# KalamBoard.net
KiCad netlist of a schematic drawn in EAGLE
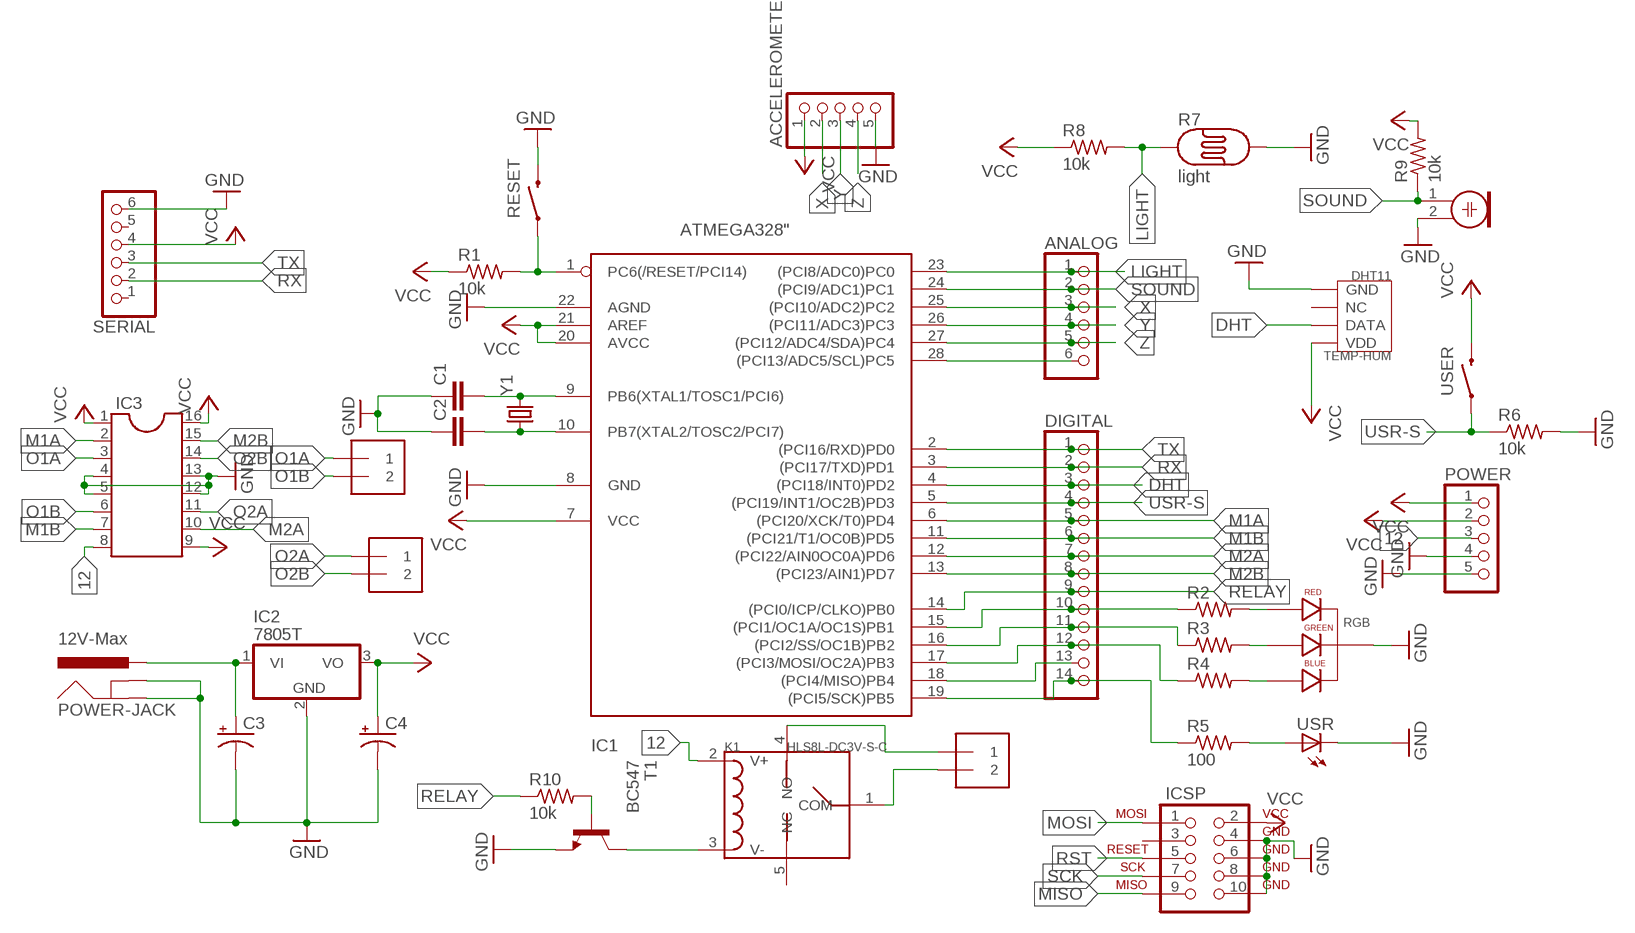
[diagram p0: schematic, sheet 1]

(export (version "E")
  (design (tool "Eeschema 10.0.6"))
  (components
    (comp (ref "ACCELEROMETER")
      (value "PINHD-1X5")
      (footprint "eagle-import:1X05")
      (libsource (lib "eagle-import") (part "PINHD-1X5"))
    )
    (comp (ref "ANALOG")
      (value "PINHD-1X6")
      (footprint "eagle-import:1X06")
      (libsource (lib "eagle-import") (part "PINHD-1X6"))
    )
    (comp (ref "C1")
      (value "0.1UF-50V-20%(PTH)KIT-EZ")
      (footprint "eagle-import:CAP-PTH-SMALL-KIT")
      (libsource (lib "eagle-import") (part "0.1UF-50V-20%(PTH)KIT-EZ"))
    )
    (comp (ref "C2")
      (value "0.1UF-50V-20%(PTH)KIT-EZ")
      (footprint "eagle-import:CAP-PTH-SMALL-KIT")
      (libsource (lib "eagle-import") (part "0.1UF-50V-20%(PTH)KIT-EZ"))
    )
    (comp (ref "C3")
      (value "10UF-25V-20%(PTH)")
      (footprint "eagle-import:CPOL-RADIAL-10UF-25V")
      (libsource (lib "eagle-import") (part "10UF-25V-20%(PTH)"))
    )
    (comp (ref "C4")
      (value "10UF-25V-20%(PTH)")
      (footprint "eagle-import:CPOL-RADIAL-10UF-25V")
      (libsource (lib "eagle-import") (part "10UF-25V-20%(PTH)"))
    )
    (comp (ref "DIGITAL")
      (value "PINHD-1X14")
      (footprint "eagle-import:1X14")
      (libsource (lib "eagle-import") (part "PINHD-1X14"))
    )
    (comp (ref "IC1")
      (value "ATMEGA328\"")
      (footprint "eagle-import:ATMEGA328")
      (libsource (lib "eagle-import") (part "ATMEGA328{dblquote}"))
    )
    (comp (ref "IC2")
      (value "7805T")
      (footprint "eagle-import:TO220H")
      (libsource (lib "eagle-import") (part "78T05"))
    )
    (comp (ref "IC3")
      (value "DIL16S")
      (footprint "eagle-import:SOCKET-16")
      (libsource (lib "eagle-import") (part "DIL16S"))
    )
    (comp (ref "ICSP")
      (value "AVR_SPI_PROG2PTH")
      (footprint "eagle-import:AVR_ICSP")
      (libsource (lib "eagle-import") (part "AVR_SPI_PROG2PTH"))
    )
    (comp (ref "K1")
      (value "HLS8L-DC3V-S-C")
      (footprint "eagle-import:REY5-19.0X15.0X15.0MM")
      (libsource (lib "eagle-import") (part "RELAY-HLS8L-DC3V-S-C(5P-19X15MM)"))
    )
    (comp (ref "MOTOR1")
      (value "1X2-3.5MM")
      (footprint "eagle-import:1X2-3.5MM")
      (libsource (lib "eagle-import") (part "1X2-3.5MM"))
    )
    (comp (ref "MOTOR2")
      (value "1X2-3.5MM")
      (footprint "eagle-import:1X2-3.5MM")
      (libsource (lib "eagle-import") (part "1X2-3.5MM"))
    )
    (comp (ref "POWER")
      (value "PINHD-1X5")
      (footprint "eagle-import:1X05")
      (libsource (lib "eagle-import") (part "PINHD-1X5"))
    )
    (comp (ref "POWER-JACK")
      (value "12V-Max")
      (footprint "eagle-import:POWER_JACK")
      (libsource (lib "eagle-import") (part "POWER_JACK{dblquote}"))
    )
    (comp (ref "R1")
      (value "10k")
      (footprint "eagle-import:RESISTOR")
      (libsource (lib "eagle-import") (part "RESISTOR1/6WATT"))
    )
    (comp (ref "R2")
      (value "RESISTOR1/6WATT")
      (footprint "eagle-import:RESISTOR")
      (libsource (lib "eagle-import") (part "RESISTOR1/6WATT"))
    )
    (comp (ref "R3")
      (value "RESISTOR1/6WATT")
      (footprint "eagle-import:RESISTOR")
      (libsource (lib "eagle-import") (part "RESISTOR1/6WATT"))
    )
    (comp (ref "R4")
      (value "RESISTOR1/6WATT")
      (footprint "eagle-import:RESISTOR")
      (libsource (lib "eagle-import") (part "RESISTOR1/6WATT"))
    )
    (comp (ref "R5")
      (value "100")
      (footprint "eagle-import:RESISTOR")
      (libsource (lib "eagle-import") (part "RESISTOR1/6WATT"))
    )
    (comp (ref "R6")
      (value "10k")
      (footprint "eagle-import:RESISTOR")
      (libsource (lib "eagle-import") (part "RESISTOR1/6WATT"))
    )
    (comp (ref "R7")
      (value "light")
      (footprint "eagle-import:PHOTOCELL")
      (libsource (lib "eagle-import") (part "PHOTOCELLPTH"))
    )
    (comp (ref "R8")
      (value "10k")
      (footprint "eagle-import:RESISTOR")
      (libsource (lib "eagle-import") (part "RESISTOR1/6WATT"))
    )
    (comp (ref "R9")
      (value "10k")
      (footprint "eagle-import:RESISTOR")
      (libsource (lib "eagle-import") (part "RESISTOR1/6WATT"))
    )
    (comp (ref "R10")
      (value "10k")
      (footprint "eagle-import:RESISTOR")
      (libsource (lib "eagle-import") (part "RESISTOR1/6WATT"))
    )
    (comp (ref "RELAY")
      (value "1X2-3.5MM")
      (footprint "eagle-import:1X2-3.5MM")
      (libsource (lib "eagle-import") (part "1X2-3.5MM"))
    )
    (comp (ref "RESET")
      (value "MOMENTARY_SWITCH\"")
      (footprint "eagle-import:MOMENTARY_SWITCH")
      (libsource (lib "eagle-import") (part "MOMENTARY_SWITCH{dblquote}"))
    )
    (comp (ref "RGB")
      (value "LED-RGB-CC-THRUDIFFUSE")
      (footprint "eagle-import:LED-RGB-THRU")
      (libsource (lib "eagle-import") (part "LED-RGB-CC-THRUDIFFUSE"))
    )
    (comp (ref "SERIAL")
      (value "PINHD-1X6")
      (footprint "eagle-import:1X06")
      (libsource (lib "eagle-import") (part "PINHD-1X6"))
    )
    (comp (ref "SOUND")
      (value "ELECTRET_MICROPHON-F6050AP")
      (footprint "eagle-import:F6050AP")
      (libsource (lib "eagle-import") (part "ELECTRET_MICROPHON-F6050AP"))
    )
    (comp (ref "T1")
      (value "BC547")
      (footprint "eagle-import:TO92")
      (libsource (lib "eagle-import") (part "BC547"))
    )
    (comp (ref "TEMP-HUM")
      (value "DHT11")
      (footprint "eagle-import:SNR4-2.54-15.5X12.0X5.5MM")
      (libsource (lib "eagle-import") (part "TEM-HUM-DHT11(4P-15.5X12.0MM)"))
    )
    (comp (ref "USER")
      (value "MOMENTARY_SWITCH\"")
      (footprint "eagle-import:MOMENTARY_SWITCH")
      (libsource (lib "eagle-import") (part "MOMENTARY_SWITCH{dblquote}"))
    )
    (comp (ref "USR")
      (value "LED3MM")
      (footprint "eagle-import:LED")
      (libsource (lib "eagle-import") (part "LED3MM"))
    )
    (comp (ref "Y1")
      (value "CRYSTALHC49US")
      (footprint "eagle-import:HC49US")
      (libsource (lib "eagle-import") (part "CRYSTALHC49US"))
    )
  )
  (nets
    (net (code "1") (name "12") (class "Default")
      (node (ref "C3") (pin "1") (pinfunction "+_1") (pintype "passive"))
      (node (ref "IC2") (pin "1") (pinfunction "VI_1") (pintype "input"))
      (node (ref "IC3") (pin "8") (pinfunction "8_8") (pintype "passive"))
      (node (ref "K1") (pin "2") (pinfunction "V+_2") (pintype "bidirectional"))
      (node (ref "POWER") (pin "3") (pinfunction "3_3") (pintype "passive"))
      (node (ref "POWER-JACK") (pin "PWR") (pinfunction "PWR_PWR") (pintype "bidirectional"))
    )
    (net (code "2") (name "DHT") (class "Default")
      (node (ref "DIGITAL") (pin "3") (pinfunction "3_3") (pintype "passive"))
      (node (ref "IC1") (pin "4") (pinfunction "(PCI18/INT0)PD2_4") (pintype "bidirectional"))
      (node (ref "TEMP-HUM") (pin "2") (pinfunction "DATA_2") (pintype "bidirectional"))
    )
    (net (code "3") (name "GND") (class "Default")
      (node (ref "ACCELEROMETER") (pin "5") (pinfunction "5_5") (pintype "passive"))
      (node (ref "C1") (pin "1") (pinfunction "1_1") (pintype "passive"))
      (node (ref "C2") (pin "1") (pinfunction "1_1") (pintype "passive"))
      (node (ref "C3") (pin "2") (pinfunction "-_2") (pintype "passive"))
      (node (ref "C4") (pin "2") (pinfunction "-_2") (pintype "passive"))
      (node (ref "IC1") (pin "22") (pinfunction "AGND_22") (pintype "bidirectional"))
      (node (ref "IC1") (pin "8") (pinfunction "GND_8") (pintype "bidirectional"))
      (node (ref "IC2") (pin "2") (pinfunction "GND_2") (pintype "passive"))
      (node (ref "IC3") (pin "12") (pinfunction "12_12") (pintype "passive"))
      (node (ref "IC3") (pin "13") (pinfunction "13_13") (pintype "passive"))
      (node (ref "IC3") (pin "4") (pinfunction "4_4") (pintype "passive"))
      (node (ref "IC3") (pin "5") (pinfunction "5_5") (pintype "passive"))
      (node (ref "ICSP") (pin "10") (pinfunction "GND_10") (pintype "power_in"))
      (node (ref "ICSP") (pin "4") (pinfunction "GND_4") (pintype "power_in"))
      (node (ref "ICSP") (pin "6") (pinfunction "GND_6") (pintype "power_in"))
      (node (ref "ICSP") (pin "8") (pinfunction "GND_8") (pintype "power_in"))
      (node (ref "POWER") (pin "4") (pinfunction "4_4") (pintype "passive"))
      (node (ref "POWER") (pin "5") (pinfunction "5_5") (pintype "passive"))
      (node (ref "POWER-JACK") (pin "GND") (pinfunction "GND_GND") (pintype "bidirectional"))
      (node (ref "POWER-JACK") (pin "GNDBREAK") (pinfunction "GNDBREAK_GNDBREAK") (pintype "bidirectional"))
      (node (ref "R6") (pin "2") (pinfunction "2_2") (pintype "passive"))
      (node (ref "R7") (pin "2") (pinfunction "P$2_2") (pintype "bidirectional"))
      (node (ref "RESET") (pin "3") (pinfunction "2_3") (pintype "passive"))
      (node (ref "RGB") (pin "2") (pinfunction "CATHODE_2") (pintype "bidirectional"))
      (node (ref "SERIAL") (pin "6") (pinfunction "6_6") (pintype "passive"))
      (node (ref "SOUND") (pin "2") (pinfunction "2_2") (pintype "passive"))
      (node (ref "T1") (pin "1") (pinfunction "E_1") (pintype "passive"))
      (node (ref "TEMP-HUM") (pin "4") (pinfunction "GND_4") (pintype "power_in"))
      (node (ref "USR") (pin "K") (pinfunction "C_K") (pintype "passive"))
    )
    (net (code "4") (name "LIGHT") (class "Default")
      (node (ref "ANALOG") (pin "1") (pinfunction "1_1") (pintype "passive"))
      (node (ref "IC1") (pin "23") (pinfunction "(PCI8/ADC0)PC0_23") (pintype "bidirectional"))
      (node (ref "R7") (pin "1") (pinfunction "P$1_1") (pintype "bidirectional"))
      (node (ref "R8") (pin "2") (pinfunction "2_2") (pintype "passive"))
    )
    (net (code "5") (name "M1A") (class "Default")
      (node (ref "DIGITAL") (pin "5") (pinfunction "5_5") (pintype "passive"))
      (node (ref "IC1") (pin "6") (pinfunction "(PCI20/XCK/T0)PD4_6") (pintype "bidirectional"))
      (node (ref "IC3") (pin "2") (pinfunction "2_2") (pintype "passive"))
    )
    (net (code "6") (name "M1B") (class "Default")
      (node (ref "DIGITAL") (pin "6") (pinfunction "6_6") (pintype "passive"))
      (node (ref "IC1") (pin "11") (pinfunction "(PCI21/T1/OC0B)PD5_11") (pintype "bidirectional"))
      (node (ref "IC3") (pin "7") (pinfunction "7_7") (pintype "passive"))
    )
    (net (code "7") (name "M2A") (class "Default")
      (node (ref "DIGITAL") (pin "7") (pinfunction "7_7") (pintype "passive"))
      (node (ref "IC1") (pin "12") (pinfunction "(PCI22/AIN0OC0A)PD6_12") (pintype "bidirectional"))
      (node (ref "IC3") (pin "10") (pinfunction "10_10") (pintype "passive"))
    )
    (net (code "8") (name "M2B") (class "Default")
      (node (ref "DIGITAL") (pin "8") (pinfunction "8_8") (pintype "passive"))
      (node (ref "IC1") (pin "13") (pinfunction "(PCI23/AIN1)PD7_13") (pintype "bidirectional"))
      (node (ref "IC3") (pin "15") (pinfunction "15_15") (pintype "passive"))
    )
    (net (code "9") (name "MISO") (class "Default")
      (node (ref "DIGITAL") (pin "13") (pinfunction "13_13") (pintype "passive"))
      (node (ref "IC1") (pin "18") (pinfunction "(PCI4/MISO)PB4_18") (pintype "bidirectional"))
      (node (ref "ICSP") (pin "9") (pinfunction "MISO_9") (pintype "passive"))
    )
    (net (code "10") (name "MOSI") (class "Default")
      (node (ref "DIGITAL") (pin "12") (pinfunction "12_12") (pintype "passive"))
      (node (ref "IC1") (pin "17") (pinfunction "(PCI3/MOSI/OC2A)PB3_17") (pintype "bidirectional"))
      (node (ref "ICSP") (pin "1") (pinfunction "MOSI_1") (pintype "passive"))
      (node (ref "R4") (pin "1") (pinfunction "1_1") (pintype "passive"))
    )
    (net (code "11") (name "Net-(IC1-(PCI1{slash}OC1A{slash}OC1S)PB1)") (class "Default")
      (node (ref "DIGITAL") (pin "10") (pinfunction "10_10") (pintype "passive"))
      (node (ref "IC1") (pin "15") (pinfunction "(PCI1/OC1A/OC1S)PB1_15") (pintype "bidirectional"))
      (node (ref "R2") (pin "1") (pinfunction "1_1") (pintype "passive"))
    )
    (net (code "12") (name "Net-(IC1-(PCI2{slash}SS{slash}OC1B)PB2)") (class "Default")
      (node (ref "DIGITAL") (pin "11") (pinfunction "11_11") (pintype "passive"))
      (node (ref "IC1") (pin "16") (pinfunction "(PCI2/SS/OC1B)PB2_16") (pintype "bidirectional"))
      (node (ref "R3") (pin "1") (pinfunction "1_1") (pintype "passive"))
    )
    (net (code "13") (name "Net-(IC1-(PCI13{slash}ADC5{slash}SCL)PC5)") (class "Default")
      (node (ref "ANALOG") (pin "6") (pinfunction "6_6") (pintype "passive"))
      (node (ref "IC1") (pin "28") (pinfunction "(PCI13/ADC5/SCL)PC5_28") (pintype "bidirectional"))
    )
    (net (code "14") (name "Net-(IC1-PB6(XTAL1{slash}TOSC1{slash}PCI6))") (class "Default")
      (node (ref "C1") (pin "2") (pinfunction "2_2") (pintype "passive"))
      (node (ref "IC1") (pin "9") (pinfunction "PB6(XTAL1/TOSC1/PCI6)_9") (pintype "bidirectional"))
      (node (ref "Y1") (pin "2") (pinfunction "2_2") (pintype "passive"))
    )
    (net (code "15") (name "Net-(IC1-PB7(XTAL2{slash}TOSC2{slash}PCI7))") (class "Default")
      (node (ref "C2") (pin "2") (pinfunction "2_2") (pintype "passive"))
      (node (ref "IC1") (pin "10") (pinfunction "PB7(XTAL2/TOSC2/PCI7)_10") (pintype "bidirectional"))
      (node (ref "Y1") (pin "1") (pinfunction "1_1") (pintype "passive"))
    )
    (net (code "16") (name "Net-(K1-COM)") (class "Default")
      (node (ref "K1") (pin "1") (pinfunction "COM_1") (pintype "bidirectional"))
      (node (ref "RELAY") (pin "2") (pinfunction "2_2") (pintype "passive"))
    )
    (net (code "17") (name "Net-(K1-NO)") (class "Default")
      (node (ref "K1") (pin "4") (pinfunction "NO_4") (pintype "bidirectional"))
      (node (ref "RELAY") (pin "1") (pinfunction "1_1") (pintype "passive"))
    )
    (net (code "18") (name "Net-(K1-V-)") (class "Default")
      (node (ref "K1") (pin "3") (pinfunction "V-_3") (pintype "bidirectional"))
      (node (ref "T1") (pin "3") (pinfunction "C_3") (pintype "passive"))
    )
    (net (code "19") (name "Net-(R5-Pad2)") (class "Default")
      (node (ref "R5") (pin "2") (pinfunction "2_2") (pintype "passive"))
      (node (ref "USR") (pin "A") (pinfunction "A_A") (pintype "passive"))
    )
    (net (code "20") (name "Net-(RGB-BLUE_CATHODE)") (class "Default")
      (node (ref "R4") (pin "2") (pinfunction "2_2") (pintype "passive"))
      (node (ref "RGB") (pin "4") (pinfunction "BLUE_CATHODE_4") (pintype "bidirectional"))
    )
    (net (code "21") (name "Net-(RGB-GREEN_CATHODE)") (class "Default")
      (node (ref "R3") (pin "2") (pinfunction "2_2") (pintype "passive"))
      (node (ref "RGB") (pin "3") (pinfunction "GREEN_CATHODE_3") (pintype "bidirectional"))
    )
    (net (code "22") (name "Net-(RGB-RED_CATHODE)") (class "Default")
      (node (ref "R2") (pin "2") (pinfunction "2_2") (pintype "passive"))
      (node (ref "RGB") (pin "1") (pinfunction "RED_CATHODE_1") (pintype "bidirectional"))
    )
    (net (code "23") (name "Net-(T1-B)") (class "Default")
      (node (ref "R10") (pin "2") (pinfunction "2_2") (pintype "passive"))
      (node (ref "T1") (pin "2") (pinfunction "B_2") (pintype "passive"))
    )
    (net (code "24") (name "O1A") (class "Default")
      (node (ref "IC3") (pin "3") (pinfunction "3_3") (pintype "passive"))
      (node (ref "MOTOR1") (pin "1") (pinfunction "1_1") (pintype "passive"))
    )
    (net (code "25") (name "O1B") (class "Default")
      (node (ref "IC3") (pin "6") (pinfunction "6_6") (pintype "passive"))
      (node (ref "MOTOR1") (pin "2") (pinfunction "2_2") (pintype "passive"))
    )
    (net (code "26") (name "O2A") (class "Default")
      (node (ref "IC3") (pin "11") (pinfunction "11_11") (pintype "passive"))
      (node (ref "MOTOR2") (pin "1") (pinfunction "1_1") (pintype "passive"))
    )
    (net (code "27") (name "O2B") (class "Default")
      (node (ref "IC3") (pin "14") (pinfunction "14_14") (pintype "passive"))
      (node (ref "MOTOR2") (pin "2") (pinfunction "2_2") (pintype "passive"))
    )
    (net (code "28") (name "RELAY") (class "Default")
      (node (ref "DIGITAL") (pin "9") (pinfunction "9_9") (pintype "passive"))
      (node (ref "IC1") (pin "14") (pinfunction "(PCI0/ICP/CLKO)PB0_14") (pintype "bidirectional"))
      (node (ref "R10") (pin "1") (pinfunction "1_1") (pintype "passive"))
    )
    (net (code "29") (name "RST") (class "Default")
      (node (ref "IC1") (pin "1") (pinfunction "PC6(/RESET/PCI14)_1") (pintype "bidirectional"))
      (node (ref "ICSP") (pin "5") (pinfunction "RESET_5") (pintype "passive"))
      (node (ref "R1") (pin "2") (pinfunction "2_2") (pintype "passive"))
      (node (ref "RESET") (pin "1") (pinfunction "1_1") (pintype "passive"))
    )
    (net (code "30") (name "RX") (class "Default")
      (node (ref "DIGITAL") (pin "2") (pinfunction "2_2") (pintype "passive"))
      (node (ref "IC1") (pin "3") (pinfunction "(PCI17/TXD)PD1_3") (pintype "bidirectional"))
      (node (ref "SERIAL") (pin "2") (pinfunction "2_2") (pintype "passive"))
    )
    (net (code "31") (name "SCK") (class "Default")
      (node (ref "DIGITAL") (pin "14") (pinfunction "14_14") (pintype "passive"))
      (node (ref "IC1") (pin "19") (pinfunction "(PCI5/SCK)PB5_19") (pintype "bidirectional"))
      (node (ref "ICSP") (pin "7") (pinfunction "SCK_7") (pintype "passive"))
      (node (ref "R5") (pin "1") (pinfunction "1_1") (pintype "passive"))
    )
    (net (code "32") (name "SOUND") (class "Default")
      (node (ref "ANALOG") (pin "2") (pinfunction "2_2") (pintype "passive"))
      (node (ref "IC1") (pin "24") (pinfunction "(PCI9/ADC1)PC1_24") (pintype "bidirectional"))
      (node (ref "R9") (pin "1") (pinfunction "1_1") (pintype "passive"))
      (node (ref "SOUND") (pin "1") (pinfunction "1_1") (pintype "passive"))
    )
    (net (code "33") (name "TX") (class "Default")
      (node (ref "DIGITAL") (pin "1") (pinfunction "1_1") (pintype "passive"))
      (node (ref "IC1") (pin "2") (pinfunction "(PCI16/RXD)PD0_2") (pintype "bidirectional"))
      (node (ref "SERIAL") (pin "3") (pinfunction "3_3") (pintype "passive"))
    )
    (net (code "34") (name "USR-S") (class "Default")
      (node (ref "DIGITAL") (pin "4") (pinfunction "4_4") (pintype "passive"))
      (node (ref "IC1") (pin "5") (pinfunction "(PCI19/INT1/OC2B)PD3_5") (pintype "bidirectional"))
      (node (ref "R6") (pin "1") (pinfunction "1_1") (pintype "passive"))
      (node (ref "USER") (pin "1") (pinfunction "1_1") (pintype "passive"))
    )
    (net (code "35") (name "VCC") (class "Default")
      (node (ref "ACCELEROMETER") (pin "1") (pinfunction "1_1") (pintype "passive"))
      (node (ref "C4") (pin "1") (pinfunction "+_1") (pintype "passive"))
      (node (ref "IC1") (pin "20") (pinfunction "AVCC_20") (pintype "bidirectional"))
      (node (ref "IC1") (pin "21") (pinfunction "AREF_21") (pintype "bidirectional"))
      (node (ref "IC1") (pin "7") (pinfunction "VCC_7") (pintype "bidirectional"))
      (node (ref "IC2") (pin "3") (pinfunction "VO_3") (pintype "passive"))
      (node (ref "IC3") (pin "1") (pinfunction "1_1") (pintype "passive"))
      (node (ref "IC3") (pin "16") (pinfunction "16_16") (pintype "passive"))
      (node (ref "IC3") (pin "9") (pinfunction "9_9") (pintype "passive"))
      (node (ref "ICSP") (pin "2") (pinfunction "VCC_2") (pintype "power_in"))
      (node (ref "POWER") (pin "1") (pinfunction "1_1") (pintype "passive"))
      (node (ref "POWER") (pin "2") (pinfunction "2_2") (pintype "passive"))
      (node (ref "R1") (pin "1") (pinfunction "1_1") (pintype "passive"))
      (node (ref "R8") (pin "1") (pinfunction "1_1") (pintype "passive"))
      (node (ref "R9") (pin "2") (pinfunction "2_2") (pintype "passive"))
      (node (ref "SERIAL") (pin "4") (pinfunction "4_4") (pintype "passive"))
      (node (ref "TEMP-HUM") (pin "1") (pinfunction "VDD_1") (pintype "power_in"))
      (node (ref "USER") (pin "3") (pinfunction "2_3") (pintype "passive"))
    )
    (net (code "36") (name "X") (class "Default")
      (node (ref "ACCELEROMETER") (pin "2") (pinfunction "2_2") (pintype "passive"))
      (node (ref "ANALOG") (pin "3") (pinfunction "3_3") (pintype "passive"))
      (node (ref "IC1") (pin "25") (pinfunction "(PCI10/ADC2)PC2_25") (pintype "bidirectional"))
    )
    (net (code "37") (name "Y") (class "Default")
      (node (ref "ACCELEROMETER") (pin "3") (pinfunction "3_3") (pintype "passive"))
      (node (ref "ANALOG") (pin "4") (pinfunction "4_4") (pintype "passive"))
      (node (ref "IC1") (pin "26") (pinfunction "(PCI11/ADC3)PC3_26") (pintype "bidirectional"))
    )
    (net (code "38") (name "Z") (class "Default")
      (node (ref "ACCELEROMETER") (pin "4") (pinfunction "4_4") (pintype "passive"))
      (node (ref "ANALOG") (pin "5") (pinfunction "5_5") (pintype "passive"))
      (node (ref "IC1") (pin "27") (pinfunction "(PCI12/ADC4/SDA)PC4_27") (pintype "bidirectional"))
    )
    (net (code "39") (name "unconnected-(ICSP-NC-Pad3)") (class "Default")
      (node (ref "ICSP") (pin "3") (pinfunction "NC_3") (pintype "no_connect"))
    )
    (net (code "40") (name "unconnected-(K1-NC-Pad5)") (class "Default")
      (node (ref "K1") (pin "5") (pinfunction "NC_5") (pintype "bidirectional"))
    )
    (net (code "41") (name "unconnected-(SERIAL-Pad1)") (class "Default")
      (node (ref "SERIAL") (pin "1") (pinfunction "1_1") (pintype "passive"))
    )
    (net (code "42") (name "unconnected-(SERIAL-Pad5)") (class "Default")
      (node (ref "SERIAL") (pin "5") (pinfunction "5_5") (pintype "passive"))
    )
    (net (code "43") (name "unconnected-(TEMP-HUM-NC-Pad3)") (class "Default")
      (node (ref "TEMP-HUM") (pin "3") (pinfunction "NC_3") (pintype "no_connect"))
    )
  )
)
